# power.net
KiCad netlist of a schematic drawn in Altium Designer
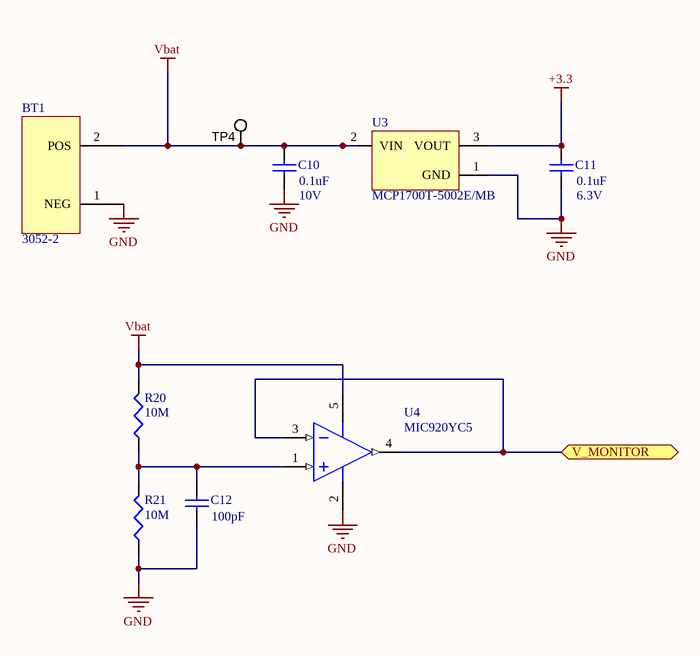
[diagram p0: power.SchDoc]

(export (version "E")
  (design (tool "Eeschema 10.0.6"))
  (components
    (comp (ref "BT1")
      (value "3052-2")
      (footprint "3025-2")
      (description "BATTERY RETNR COIN 2 CELL PC PIN")
      (fields (field (name "MPN") "3025-2") (field (name "MANUFACTURER") "Keystone Electronics"))
      (libsource (lib "CustomLib") (part "3025-2"))
    )
    (comp (ref "C10")
      (value "0.1uF")
      (footprint "1608[0603]")
      (description "Capacitor (Semiconductor SIM Model)")
      (fields
        (field (name "VOLTAGE") "10V")
        (field (name "MPN") "0603ZC104KAT2A")
        (field (name "MANUFACTURER") "AVX Corporation")
        (field (name "PUBLISHER") "Altium Limited")
      )
      (libsource (lib "Miscellaneous Devices") (part "Cap Semi"))
    )
    (comp (ref "C11")
      (value "0.1uF")
      (footprint "1608[0603]")
      (description "Capacitor (Semiconductor SIM Model)")
      (fields
        (field (name "VOLTAGE") "6.3V")
        (field (name "MPN") "06036C104KAT4A")
        (field (name "MANUFACTURER") "AVX Corporation")
        (field (name "PUBLISHER") "Altium Limited")
      )
      (libsource (lib "Miscellaneous Devices") (part "Cap Semi"))
    )
    (comp (ref "C12")
      (value "100pF")
      (footprint "0603")
      (description "Capacitor (Semiconductor SIM Model)")
      (fields
        (field (name "MPN") "0603ZC101KAT2A")
        (field (name "MANUFACTURER") "AVX Corporation")
        (field (name "PUBLISHER") "Altium Limited")
      )
      (libsource (lib "Miscellaneous Devices") (part "Cap Semi"))
    )
    (comp (ref "R20")
      (value "10M")
      (footprint "J1-0603")
      (description "Resistor")
      (fields
        (field (name "MPN") "ERJ-3GEYJ106V")
        (field (name "MANUFACTURER") "Panasonic")
        (field (name "PUBLISHER") "Altium Limited")
      )
      (libsource (lib "Miscellaneous Devices") (part "Res3"))
    )
    (comp (ref "R21")
      (value "10M")
      (footprint "J1-0603")
      (description "Resistor")
      (fields
        (field (name "MPN") "ERJ-3GEYJ106V")
        (field (name "MANUFACTURER") "Panasonic")
        (field (name "PUBLISHER") "Altium Limited")
      )
      (libsource (lib "Miscellaneous Devices") (part "Res3"))
    )
    (comp (ref "TP4")
      (value "5002")
      (footprint "Keystone5002")
      (description "Test Point, Miniature, White, TH")
      (fields (field (name "MANUFACTURER") "Keystone") (field (name "PUBLISHER") "Texas Instruments"))
      (libsource (lib "MDBU017A") (part "5002"))
    )
    (comp (ref "U3")
      (value "MCP1700T-5002E/MB")
      (footprint "SOT-89-MB3_N")
      (description "Low Quiescent Current LDO, 3-Pin SOT-89, Extended Temperature, Tape and Reel")
      (fields (field (name "MANUFACTURER") "Microchip"))
      (libsource (lib "Components - 17.05.20 - 09.28") (part "CMP-0136-00868-1"))
    )
    (comp (ref "U4")
      (value "MIC920YC5")
      (footprint "X5+1_L")
      (fields (field (name "MANUFACTURER") "Microchip") (field (name "PARTNUMBER") "MIC920YC5-TR"))
      (libsource (lib "Altium Content Vault") (part "MAXM-MAX4230-5"))
    )
  )
  (nets
    (net (code "1") (name "+3.3") (class "Default")
      (node (ref "C11") (pin "2") (pinfunction "2_2") (pintype "passive"))
      (node (ref "U3") (pin "3") (pinfunction "VOUT_3") (pintype "power_in"))
    )
    (net (code "2") (name "/V_MONITOR") (class "Default")
      (node (ref "U4") (pin "3") (pinfunction "IN-_3") (pintype "input"))
      (node (ref "U4") (pin "4") (pinfunction "OUT_4") (pintype "output"))
    )
    (net (code "3") (name "GND") (class "Default")
      (node (ref "BT1") (pin "1") (pinfunction "NEG_1") (pintype "passive"))
      (node (ref "C10") (pin "1") (pinfunction "1_1") (pintype "passive"))
      (node (ref "C11") (pin "1") (pinfunction "1_1") (pintype "passive"))
      (node (ref "C12") (pin "1") (pinfunction "1_1") (pintype "passive"))
      (node (ref "R21") (pin "1") (pinfunction "1_1") (pintype "passive"))
      (node (ref "U3") (pin "1") (pinfunction "GND_1") (pintype "power_in"))
      (node (ref "U4") (pin "2") (pinfunction "VSS_2") (pintype "power_in"))
    )
    (net (code "4") (name "Net-(U4-IN+)") (class "Default")
      (node (ref "C12") (pin "2") (pinfunction "2_2") (pintype "passive"))
      (node (ref "R20") (pin "1") (pinfunction "1_1") (pintype "passive"))
      (node (ref "R21") (pin "2") (pinfunction "2_2") (pintype "passive"))
      (node (ref "U4") (pin "1") (pinfunction "IN+_1") (pintype "input"))
    )
    (net (code "5") (name "Vbat") (class "Default")
      (node (ref "BT1") (pin "2") (pinfunction "POS_2") (pintype "passive"))
      (node (ref "C10") (pin "2") (pinfunction "2_2") (pintype "passive"))
      (node (ref "R20") (pin "2") (pinfunction "2_2") (pintype "passive"))
      (node (ref "TP4") (pin "1") (pintype "passive"))
      (node (ref "U3") (pin "2") (pinfunction "VIN_2") (pintype "power_in"))
      (node (ref "U4") (pin "5") (pinfunction "VDD_5") (pintype "power_in"))
    )
  )
)
